# Power.net
KiCad netlist of a schematic drawn in Altium Designer
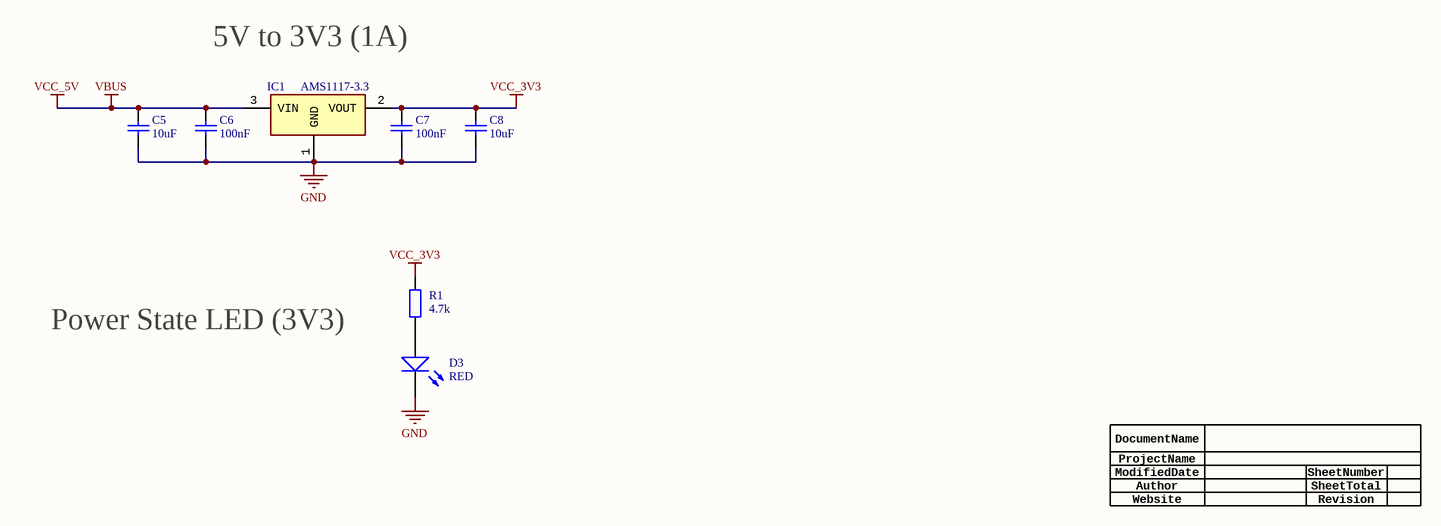
[diagram p0: Power.SchDoc]

(export (version "E")
  (design (tool "Eeschema 10.0.6"))
  (components
    (comp (ref "C5")
      (value "10uF")
      (footprint "CAP-0603")
      (description "贴片电容")
      (libsource (lib "Power_Lib_Altium") (part "CAP"))
    )
    (comp (ref "C6")
      (value "100nF")
      (footprint "CAP-0603")
      (description "贴片电容")
      (libsource (lib "Power_Lib_Altium") (part "CAP"))
    )
    (comp (ref "C7")
      (value "100nF")
      (footprint "CAP-0603")
      (description "贴片电容")
      (libsource (lib "Power_Lib_Altium") (part "CAP"))
    )
    (comp (ref "C8")
      (value "10uF")
      (footprint "CAP-0603")
      (description "贴片电容")
      (libsource (lib "Power_Lib_Altium") (part "CAP"))
    )
    (comp (ref "D3")
      (value "RED")
      (footprint "LED-0603")
      (description "发光二极管")
      (libsource (lib "Power_Lib_Altium") (part "LED"))
    )
    (comp (ref "IC1")
      (value "AMS1117-3.3")
      (footprint "SOT-223")
      (description "AMS1117-3.3 1.0A")
      (fields (field (name "MANUFACTURER_PART_NUMBER") "SI2302DS") (field (name "RS PART NUMBER") "7983053P"))
      (libsource (lib "Power_Lib_Altium") (part "AMS1117"))
    )
    (comp (ref "R1")
      (value "4.7k")
      (footprint "R-0603")
      (description "贴片电阻")
      (libsource (lib "Power_Lib_Altium") (part "RES"))
    )
  )
  (nets
    (net (code "1") (name "GND") (class "Default")
      (node (ref "C5") (pin "1") (pinfunction "1_1") (pintype "passive"))
      (node (ref "C6") (pin "1") (pinfunction "1_1") (pintype "passive"))
      (node (ref "C7") (pin "1") (pinfunction "1_1") (pintype "passive"))
      (node (ref "C8") (pin "1") (pinfunction "1_1") (pintype "passive"))
      (node (ref "D3") (pin "K") (pinfunction "K_K") (pintype "passive"))
      (node (ref "IC1") (pin "1") (pinfunction "GND_1") (pintype "passive"))
    )
    (net (code "2") (name "Net-(D3-PadA)") (class "Default")
      (node (ref "D3") (pin "A") (pinfunction "A_A") (pintype "passive"))
      (node (ref "R1") (pin "1") (pinfunction "1_1") (pintype "passive"))
    )
    (net (code "3") (name "VBUS") (class "Default")
      (node (ref "C5") (pin "2") (pinfunction "2_2") (pintype "passive"))
      (node (ref "C6") (pin "2") (pinfunction "2_2") (pintype "passive"))
      (node (ref "IC1") (pin "3") (pinfunction "VIN_3") (pintype "passive"))
    )
    (net (code "4") (name "VCC_3V3") (class "Default")
      (node (ref "C7") (pin "2") (pinfunction "2_2") (pintype "passive"))
      (node (ref "C8") (pin "2") (pinfunction "2_2") (pintype "passive"))
      (node (ref "IC1") (pin "2") (pinfunction "VOUT_2") (pintype "passive"))
      (node (ref "R1") (pin "2") (pinfunction "2_2") (pintype "passive"))
    )
  )
)
